# pineapple_2_model_2013_rev_1.net
KiCad netlist of a schematic drawn in EAGLE
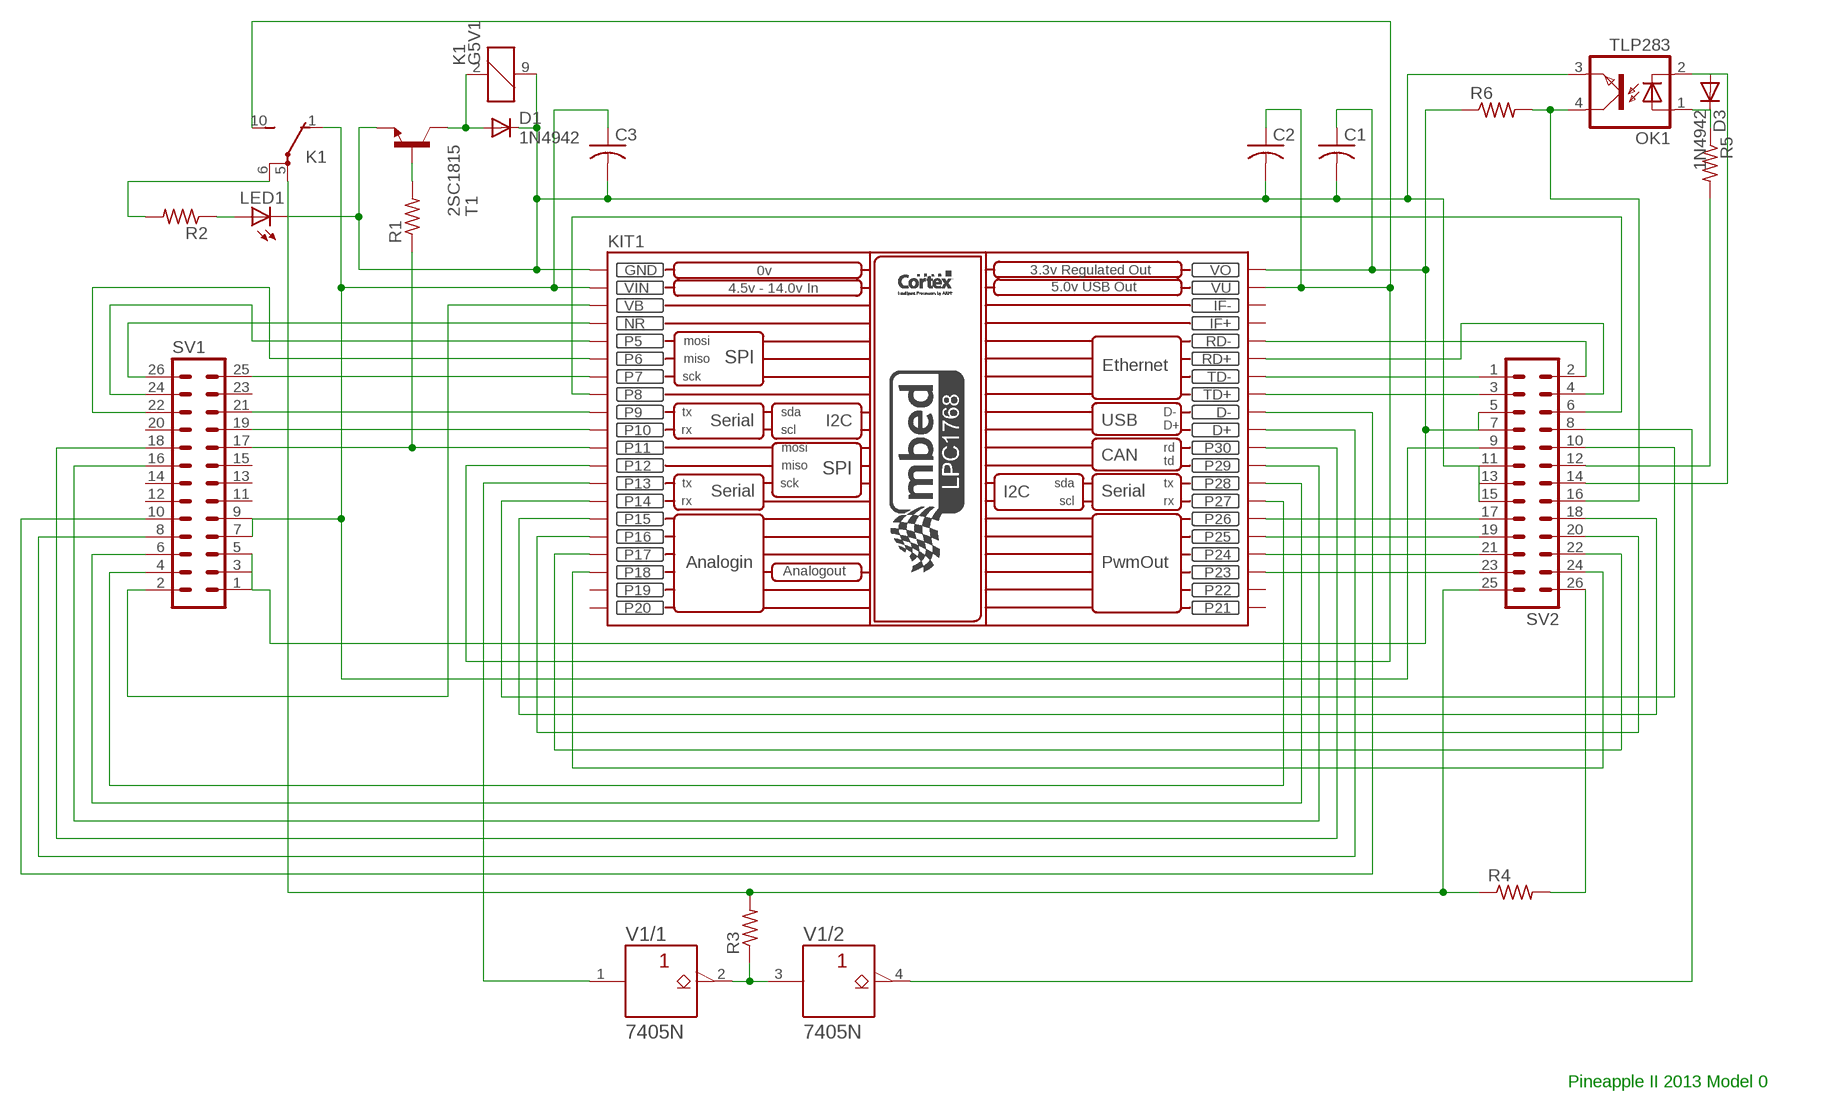
[diagram p0: schematic, sheet 1]

(export (version "E")
  (design (tool "Eeschema 10.0.6"))
  (components
    (comp (ref "C1")
      (value "C-US025-024X044")
      (footprint "eagle-import:C025-024X044")
      (libsource (lib "eagle-import") (part "C-US025-024X044"))
    )
    (comp (ref "C2")
      (value "C-US025-024X044")
      (footprint "eagle-import:C025-024X044")
      (libsource (lib "eagle-import") (part "C-US025-024X044"))
    )
    (comp (ref "C3")
      (value "C-US050-024X044")
      (footprint "eagle-import:C050-024X044")
      (libsource (lib "eagle-import") (part "C-US050-024X044"))
    )
    (comp (ref "D1")
      (value "1N4942")
      (footprint "eagle-import:DO41-10")
      (libsource (lib "eagle-import") (part "1N4942"))
    )
    (comp (ref "D3")
      (value "1N4942")
      (footprint "eagle-import:DO41-10")
      (libsource (lib "eagle-import") (part "1N4942"))
    )
    (comp (ref "K1")
      (value "G5V1")
      (footprint "eagle-import:G5V1")
      (fields (field (name "MPN") "G5V-1-DC24"))
      (libsource (lib "eagle-import") (part "G5V1"))
    )
    (comp (ref "KIT1")
      (value "MBED_NXP_LPC1768")
      (footprint "eagle-import:MBED-KIT")
      (libsource (lib "eagle-import") (part "MBED_NXP_LPC1768"))
    )
    (comp (ref "LED1")
      (value "LED3MM")
      (footprint "eagle-import:LED3MM")
      (libsource (lib "eagle-import") (part "LED3MM"))
    )
    (comp (ref "OK1")
      (value "TLP283")
      (footprint "eagle-import:MINI-FLAT-4")
      (libsource (lib "eagle-import") (part "TLP283"))
    )
    (comp (ref "R1")
      (value "R-US_0204/5")
      (footprint "eagle-import:0204_5")
      (libsource (lib "eagle-import") (part "R-US_0204/5"))
    )
    (comp (ref "R2")
      (value "R-US_0204/5")
      (footprint "eagle-import:0204_5")
      (libsource (lib "eagle-import") (part "R-US_0204/5"))
    )
    (comp (ref "R3")
      (value "R-US_0204/5")
      (footprint "eagle-import:0204_5")
      (libsource (lib "eagle-import") (part "R-US_0204/5"))
    )
    (comp (ref "R4")
      (value "R-US_0204/5")
      (footprint "eagle-import:0204_5")
      (libsource (lib "eagle-import") (part "R-US_0204/5"))
    )
    (comp (ref "R5")
      (value "R-US_0204/5")
      (footprint "eagle-import:0204_5")
      (libsource (lib "eagle-import") (part "R-US_0204/5"))
    )
    (comp (ref "R6")
      (value "R-US_0204/5")
      (footprint "eagle-import:0204_5")
      (libsource (lib "eagle-import") (part "R-US_0204/5"))
    )
    (comp (ref "SV1")
      (value "ML26L")
      (footprint "eagle-import:ML26L")
      (libsource (lib "eagle-import") (part "ML26L"))
    )
    (comp (ref "SV2")
      (value "ML26L")
      (footprint "eagle-import:ML26L")
      (libsource (lib "eagle-import") (part "ML26L"))
    )
    (comp (ref "T1")
      (value "2SC1815")
      (footprint "eagle-import:TO92-ECB")
      (libsource (lib "eagle-import") (part "2SC1815"))
    )
    (comp (ref "V1")
      (value "7405N")
      (footprint "eagle-import:DIL14")
      (libsource (lib "eagle-import") (part "7405N"))
    )
  )
  (nets
    (net (code "1") (name "Net-(K1A-1)") (class "Default")
      (node (ref "D1") (pin "A") (pinfunction "A_A") (pintype "passive"))
      (node (ref "K1") (pin "2") (pinfunction "1_2") (pintype "passive"))
      (node (ref "T1") (pin "C") (pinfunction "C_C") (pintype "passive"))
    )
    (net (code "2") (name "Net-(K1A-2)") (class "Default")
      (node (ref "C1") (pin "2") (pinfunction "2_2") (pintype "passive"))
      (node (ref "C2") (pin "2") (pinfunction "2_2") (pintype "passive"))
      (node (ref "C3") (pin "2") (pinfunction "2_2") (pintype "passive"))
      (node (ref "D1") (pin "C") (pinfunction "C_C") (pintype "passive"))
      (node (ref "K1") (pin "9") (pinfunction "2_9") (pintype "passive"))
      (node (ref "KIT1") (pin "GND") (pinfunction "GND_GND") (pintype "power_in"))
      (node (ref "LED1") (pin "K") (pinfunction "C_K") (pintype "passive"))
      (node (ref "OK1") (pin "3") (pinfunction "EMIT_3") (pintype "passive"))
      (node (ref "SV2") (pin "11") (pinfunction "11_11") (pintype "passive"))
      (node (ref "SV2") (pin "13") (pinfunction "13_13") (pintype "passive"))
      (node (ref "SV2") (pin "15") (pinfunction "15_15") (pintype "passive"))
      (node (ref "T1") (pin "E") (pinfunction "E_E") (pintype "passive"))
    )
    (net (code "3") (name "Net-(K1B-O)") (class "Default")
      (node (ref "C3") (pin "1") (pinfunction "1_1") (pintype "passive"))
      (node (ref "K1") (pin "1") (pinfunction "O_1") (pintype "passive"))
      (node (ref "KIT1") (pin "VIN") (pinfunction "VIN_VIN") (pintype "power_in"))
      (node (ref "SV1") (pin "7") (pinfunction "7_7") (pintype "passive"))
      (node (ref "SV1") (pin "9") (pinfunction "9_9") (pintype "passive"))
      (node (ref "SV2") (pin "9") (pinfunction "9_9") (pintype "passive"))
    )
    (net (code "4") (name "Net-(K1B-P-Pad5)") (class "Default")
      (node (ref "K1") (pin "5") (pinfunction "P_5") (pintype "passive"))
      (node (ref "R3") (pin "2") (pinfunction "2_2") (pintype "passive"))
      (node (ref "R4") (pin "1") (pinfunction "1_1") (pintype "passive"))
      (node (ref "SV2") (pin "25") (pinfunction "25_25") (pintype "passive"))
    )
    (net (code "5") (name "Net-(K1B-P-Pad6)") (class "Default")
      (node (ref "K1") (pin "6") (pinfunction "P_6") (pintype "passive"))
      (node (ref "R2") (pin "2") (pinfunction "2_2") (pintype "passive"))
    )
    (net (code "6") (name "Net-(K1B-S)") (class "Default")
      (node (ref "C2") (pin "1") (pinfunction "1_1") (pintype "passive"))
      (node (ref "K1") (pin "10") (pinfunction "S_10") (pintype "passive"))
      (node (ref "KIT1") (pin "P$12") (pinfunction "P12_P$12") (pintype "bidirectional"))
      (node (ref "KIT1") (pin "VU") (pinfunction "VU_VU") (pintype "power_in"))
    )
    (net (code "7") (name "Net-(KIT1-P5)") (class "Default")
      (node (ref "KIT1") (pin "P$5") (pinfunction "P5_P$5") (pintype "bidirectional"))
      (node (ref "SV1") (pin "24") (pinfunction "24_24") (pintype "passive"))
    )
    (net (code "8") (name "Net-(KIT1-P6)") (class "Default")
      (node (ref "KIT1") (pin "P$6") (pinfunction "P6_P$6") (pintype "bidirectional"))
      (node (ref "SV1") (pin "22") (pinfunction "22_22") (pintype "passive"))
    )
    (net (code "9") (name "Net-(KIT1-P7)") (class "Default")
      (node (ref "KIT1") (pin "P$7") (pinfunction "P7_P$7") (pintype "bidirectional"))
      (node (ref "SV1") (pin "25") (pinfunction "25_25") (pintype "passive"))
    )
    (net (code "10") (name "Net-(KIT1-P8)") (class "Default")
      (node (ref "KIT1") (pin "P$8") (pinfunction "P8_P$8") (pintype "bidirectional"))
      (node (ref "SV2") (pin "6") (pinfunction "6_6") (pintype "passive"))
    )
    (net (code "11") (name "Net-(KIT1-P9)") (class "Default")
      (node (ref "KIT1") (pin "P$9") (pinfunction "P9_P$9") (pintype "bidirectional"))
      (node (ref "SV1") (pin "21") (pinfunction "21_21") (pintype "passive"))
    )
    (net (code "12") (name "Net-(KIT1-P10)") (class "Default")
      (node (ref "KIT1") (pin "P$10") (pinfunction "P10_P$10") (pintype "bidirectional"))
      (node (ref "SV1") (pin "19") (pinfunction "19_19") (pintype "passive"))
    )
    (net (code "13") (name "Net-(KIT1-P11)") (class "Default")
      (node (ref "KIT1") (pin "P$11") (pinfunction "P11_P$11") (pintype "bidirectional"))
      (node (ref "R1") (pin "1") (pinfunction "1_1") (pintype "passive"))
      (node (ref "SV1") (pin "17") (pinfunction "17_17") (pintype "passive"))
    )
    (net (code "14") (name "Net-(KIT1-P13)") (class "Default")
      (node (ref "KIT1") (pin "P$13") (pinfunction "P13_P$13") (pintype "bidirectional"))
      (node (ref "V1") (pin "1") (pinfunction "A_1") (pintype "input"))
    )
    (net (code "15") (name "Net-(KIT1-P14)") (class "Default")
      (node (ref "KIT1") (pin "P$14") (pinfunction "P14_P$14") (pintype "bidirectional"))
      (node (ref "SV2") (pin "10") (pinfunction "10_10") (pintype "passive"))
    )
    (net (code "16") (name "Net-(KIT1-P15)") (class "Default")
      (node (ref "KIT1") (pin "P$15") (pinfunction "P15_P$15") (pintype "bidirectional"))
      (node (ref "SV2") (pin "18") (pinfunction "18_18") (pintype "passive"))
    )
    (net (code "17") (name "Net-(KIT1-P16)") (class "Default")
      (node (ref "KIT1") (pin "P$16") (pinfunction "P16_P$16") (pintype "bidirectional"))
      (node (ref "SV2") (pin "20") (pinfunction "20_20") (pintype "passive"))
    )
    (net (code "18") (name "Net-(KIT1-P17)") (class "Default")
      (node (ref "KIT1") (pin "P$17") (pinfunction "P17_P$17") (pintype "bidirectional"))
      (node (ref "SV2") (pin "22") (pinfunction "22_22") (pintype "passive"))
    )
    (net (code "19") (name "Net-(KIT1-P18)") (class "Default")
      (node (ref "KIT1") (pin "P$18") (pinfunction "P18_P$18") (pintype "bidirectional"))
      (node (ref "SV2") (pin "24") (pinfunction "24_24") (pintype "passive"))
    )
    (net (code "20") (name "Net-(KIT1-P23)") (class "Default")
      (node (ref "KIT1") (pin "P$23") (pinfunction "P23_P$23") (pintype "bidirectional"))
      (node (ref "SV2") (pin "23") (pinfunction "23_23") (pintype "passive"))
    )
    (net (code "21") (name "Net-(KIT1-P24)") (class "Default")
      (node (ref "KIT1") (pin "P$24") (pinfunction "P24_P$24") (pintype "bidirectional"))
      (node (ref "SV2") (pin "21") (pinfunction "21_21") (pintype "passive"))
    )
    (net (code "22") (name "Net-(KIT1-P25)") (class "Default")
      (node (ref "KIT1") (pin "P$25") (pinfunction "P25_P$25") (pintype "bidirectional"))
      (node (ref "SV2") (pin "19") (pinfunction "19_19") (pintype "passive"))
    )
    (net (code "23") (name "Net-(KIT1-P26)") (class "Default")
      (node (ref "KIT1") (pin "P$26") (pinfunction "P26_P$26") (pintype "bidirectional"))
      (node (ref "SV2") (pin "17") (pinfunction "17_17") (pintype "passive"))
    )
    (net (code "24") (name "Net-(KIT1-P27)") (class "Default")
      (node (ref "KIT1") (pin "P$27") (pinfunction "P27_P$27") (pintype "bidirectional"))
      (node (ref "SV1") (pin "4") (pinfunction "4_4") (pintype "passive"))
    )
    (net (code "25") (name "Net-(KIT1-P28)") (class "Default")
      (node (ref "KIT1") (pin "P$28") (pinfunction "P28_P$28") (pintype "bidirectional"))
      (node (ref "SV1") (pin "6") (pinfunction "6_6") (pintype "passive"))
    )
    (net (code "26") (name "Net-(KIT1-P29)") (class "Default")
      (node (ref "KIT1") (pin "P$29") (pinfunction "P29_P$29") (pintype "bidirectional"))
      (node (ref "SV1") (pin "16") (pinfunction "16_16") (pintype "passive"))
    )
    (net (code "27") (name "Net-(KIT1-P30)") (class "Default")
      (node (ref "KIT1") (pin "P$30") (pinfunction "P30_P$30") (pintype "bidirectional"))
      (node (ref "SV1") (pin "18") (pinfunction "18_18") (pintype "passive"))
    )
    (net (code "28") (name "Net-(KIT1-PadD+)") (class "Default")
      (node (ref "KIT1") (pin "D+") (pinfunction "D+_D+") (pintype "bidirectional"))
      (node (ref "SV1") (pin "8") (pinfunction "8_8") (pintype "passive"))
    )
    (net (code "29") (name "Net-(KIT1-PadD-)") (class "Default")
      (node (ref "KIT1") (pin "D-") (pinfunction "D-_D-") (pintype "bidirectional"))
      (node (ref "SV1") (pin "10") (pinfunction "10_10") (pintype "passive"))
    )
    (net (code "30") (name "Net-(KIT1-PadNR)") (class "Default")
      (node (ref "KIT1") (pin "NR") (pinfunction "NR_NR") (pintype "power_in"))
      (node (ref "SV1") (pin "26") (pinfunction "26_26") (pintype "passive"))
    )
    (net (code "31") (name "Net-(KIT1-PadRD+)") (class "Default")
      (node (ref "KIT1") (pin "RD+") (pinfunction "RD+_RD+") (pintype "bidirectional"))
      (node (ref "SV2") (pin "4") (pinfunction "4_4") (pintype "passive"))
    )
    (net (code "32") (name "Net-(KIT1-PadRD-)") (class "Default")
      (node (ref "KIT1") (pin "RD-") (pinfunction "RD-_RD-") (pintype "bidirectional"))
      (node (ref "SV2") (pin "2") (pinfunction "2_2") (pintype "passive"))
    )
    (net (code "33") (name "Net-(KIT1-PadTD+)") (class "Default")
      (node (ref "KIT1") (pin "TD+") (pinfunction "TD+_TD+") (pintype "bidirectional"))
      (node (ref "SV2") (pin "3") (pinfunction "3_3") (pintype "passive"))
    )
    (net (code "34") (name "Net-(KIT1-PadTD-)") (class "Default")
      (node (ref "KIT1") (pin "TD-") (pinfunction "TD-_TD-") (pintype "bidirectional"))
      (node (ref "SV2") (pin "1") (pinfunction "1_1") (pintype "passive"))
    )
    (net (code "35") (name "Net-(KIT1-PadVB)") (class "Default")
      (node (ref "KIT1") (pin "VB") (pinfunction "VB_VB") (pintype "power_in"))
      (node (ref "SV1") (pin "2") (pinfunction "2_2") (pintype "passive"))
    )
    (net (code "36") (name "Net-(KIT1-VO)") (class "Default")
      (node (ref "C1") (pin "1") (pinfunction "1_1") (pintype "passive"))
      (node (ref "KIT1") (pin "VOUT") (pinfunction "VO_VOUT") (pintype "power_in"))
      (node (ref "R6") (pin "1") (pinfunction "1_1") (pintype "passive"))
      (node (ref "SV1") (pin "1") (pinfunction "1_1") (pintype "passive"))
      (node (ref "SV1") (pin "3") (pinfunction "3_3") (pintype "passive"))
      (node (ref "SV1") (pin "5") (pinfunction "5_5") (pintype "passive"))
      (node (ref "SV2") (pin "5") (pinfunction "5_5") (pintype "passive"))
      (node (ref "SV2") (pin "7") (pinfunction "7_7") (pintype "passive"))
    )
    (net (code "37") (name "Net-(LED1-PadA)") (class "Default")
      (node (ref "LED1") (pin "A") (pinfunction "A_A") (pintype "passive"))
      (node (ref "R2") (pin "1") (pinfunction "1_1") (pintype "passive"))
    )
    (net (code "38") (name "Net-(OK1-A)") (class "Default")
      (node (ref "D3") (pin "C") (pinfunction "C_C") (pintype "passive"))
      (node (ref "OK1") (pin "1") (pinfunction "A_1") (pintype "passive"))
      (node (ref "R5") (pin "1") (pinfunction "1_1") (pintype "passive"))
    )
    (net (code "39") (name "Net-(OK1-C)") (class "Default")
      (node (ref "D3") (pin "A") (pinfunction "A_A") (pintype "passive"))
      (node (ref "OK1") (pin "2") (pinfunction "C_2") (pintype "passive"))
      (node (ref "SV2") (pin "14") (pinfunction "14_14") (pintype "passive"))
    )
    (net (code "40") (name "Net-(OK1-COL)") (class "Default")
      (node (ref "OK1") (pin "4") (pinfunction "COL_4") (pintype "passive"))
      (node (ref "R6") (pin "2") (pinfunction "2_2") (pintype "passive"))
      (node (ref "SV2") (pin "16") (pinfunction "16_16") (pintype "passive"))
    )
    (net (code "41") (name "Net-(R1-Pad2)") (class "Default")
      (node (ref "R1") (pin "2") (pinfunction "2_2") (pintype "passive"))
      (node (ref "T1") (pin "B") (pinfunction "B_B") (pintype "passive"))
    )
    (net (code "42") (name "Net-(R4-Pad2)") (class "Default")
      (node (ref "R4") (pin "2") (pinfunction "2_2") (pintype "passive"))
      (node (ref "SV2") (pin "26") (pinfunction "26_26") (pintype "passive"))
    )
    (net (code "43") (name "Net-(R5-Pad2)") (class "Default")
      (node (ref "R5") (pin "2") (pinfunction "2_2") (pintype "passive"))
      (node (ref "SV2") (pin "12") (pinfunction "12_12") (pintype "passive"))
    )
    (net (code "44") (name "Net-(V1C-Y)") (class "Default")
      (node (ref "R3") (pin "1") (pinfunction "1_1") (pintype "passive"))
      (node (ref "V1") (pin "2") (pinfunction "Y_2") (pintype "open_collector"))
      (node (ref "V1") (pin "3") (pinfunction "A_3") (pintype "input"))
    )
    (net (code "45") (name "Net-(V1D-Y)") (class "Default")
      (node (ref "SV2") (pin "8") (pinfunction "8_8") (pintype "passive"))
      (node (ref "V1") (pin "4") (pinfunction "Y_4") (pintype "open_collector"))
    )
    (net (code "46") (name "unconnected-(KIT1-P19-PadP$19)") (class "Default")
      (node (ref "KIT1") (pin "P$19") (pinfunction "P19_P$19") (pintype "bidirectional"))
    )
    (net (code "47") (name "unconnected-(KIT1-P20-PadP$20)") (class "Default")
      (node (ref "KIT1") (pin "P$20") (pinfunction "P20_P$20") (pintype "bidirectional"))
    )
    (net (code "48") (name "unconnected-(KIT1-P21-PadP$21)") (class "Default")
      (node (ref "KIT1") (pin "P$21") (pinfunction "P21_P$21") (pintype "bidirectional"))
    )
    (net (code "49") (name "unconnected-(KIT1-P22-PadP$22)") (class "Default")
      (node (ref "KIT1") (pin "P$22") (pinfunction "P22_P$22") (pintype "bidirectional"))
    )
    (net (code "50") (name "unconnected-(KIT1-PadIF+)") (class "Default")
      (node (ref "KIT1") (pin "IF+") (pinfunction "IF+_IF+") (pintype "bidirectional"))
    )
    (net (code "51") (name "unconnected-(KIT1-PadIF-)") (class "Default")
      (node (ref "KIT1") (pin "IF-") (pinfunction "IF-_IF-") (pintype "bidirectional"))
    )
    (net (code "52") (name "unconnected-(SV1-Pad11)") (class "Default")
      (node (ref "SV1") (pin "11") (pinfunction "11_11") (pintype "passive"))
    )
    (net (code "53") (name "unconnected-(SV1-Pad12)") (class "Default")
      (node (ref "SV1") (pin "12") (pinfunction "12_12") (pintype "passive"))
    )
    (net (code "54") (name "unconnected-(SV1-Pad13)") (class "Default")
      (node (ref "SV1") (pin "13") (pinfunction "13_13") (pintype "passive"))
    )
    (net (code "55") (name "unconnected-(SV1-Pad14)") (class "Default")
      (node (ref "SV1") (pin "14") (pinfunction "14_14") (pintype "passive"))
    )
    (net (code "56") (name "unconnected-(SV1-Pad15)") (class "Default")
      (node (ref "SV1") (pin "15") (pinfunction "15_15") (pintype "passive"))
    )
    (net (code "57") (name "unconnected-(SV1-Pad20)") (class "Default")
      (node (ref "SV1") (pin "20") (pinfunction "20_20") (pintype "passive"))
    )
    (net (code "58") (name "unconnected-(SV1-Pad23)") (class "Default")
      (node (ref "SV1") (pin "23") (pinfunction "23_23") (pintype "passive"))
    )
  )
)
